# Sheet3.net
KiCad netlist of a schematic drawn in Altium Designer
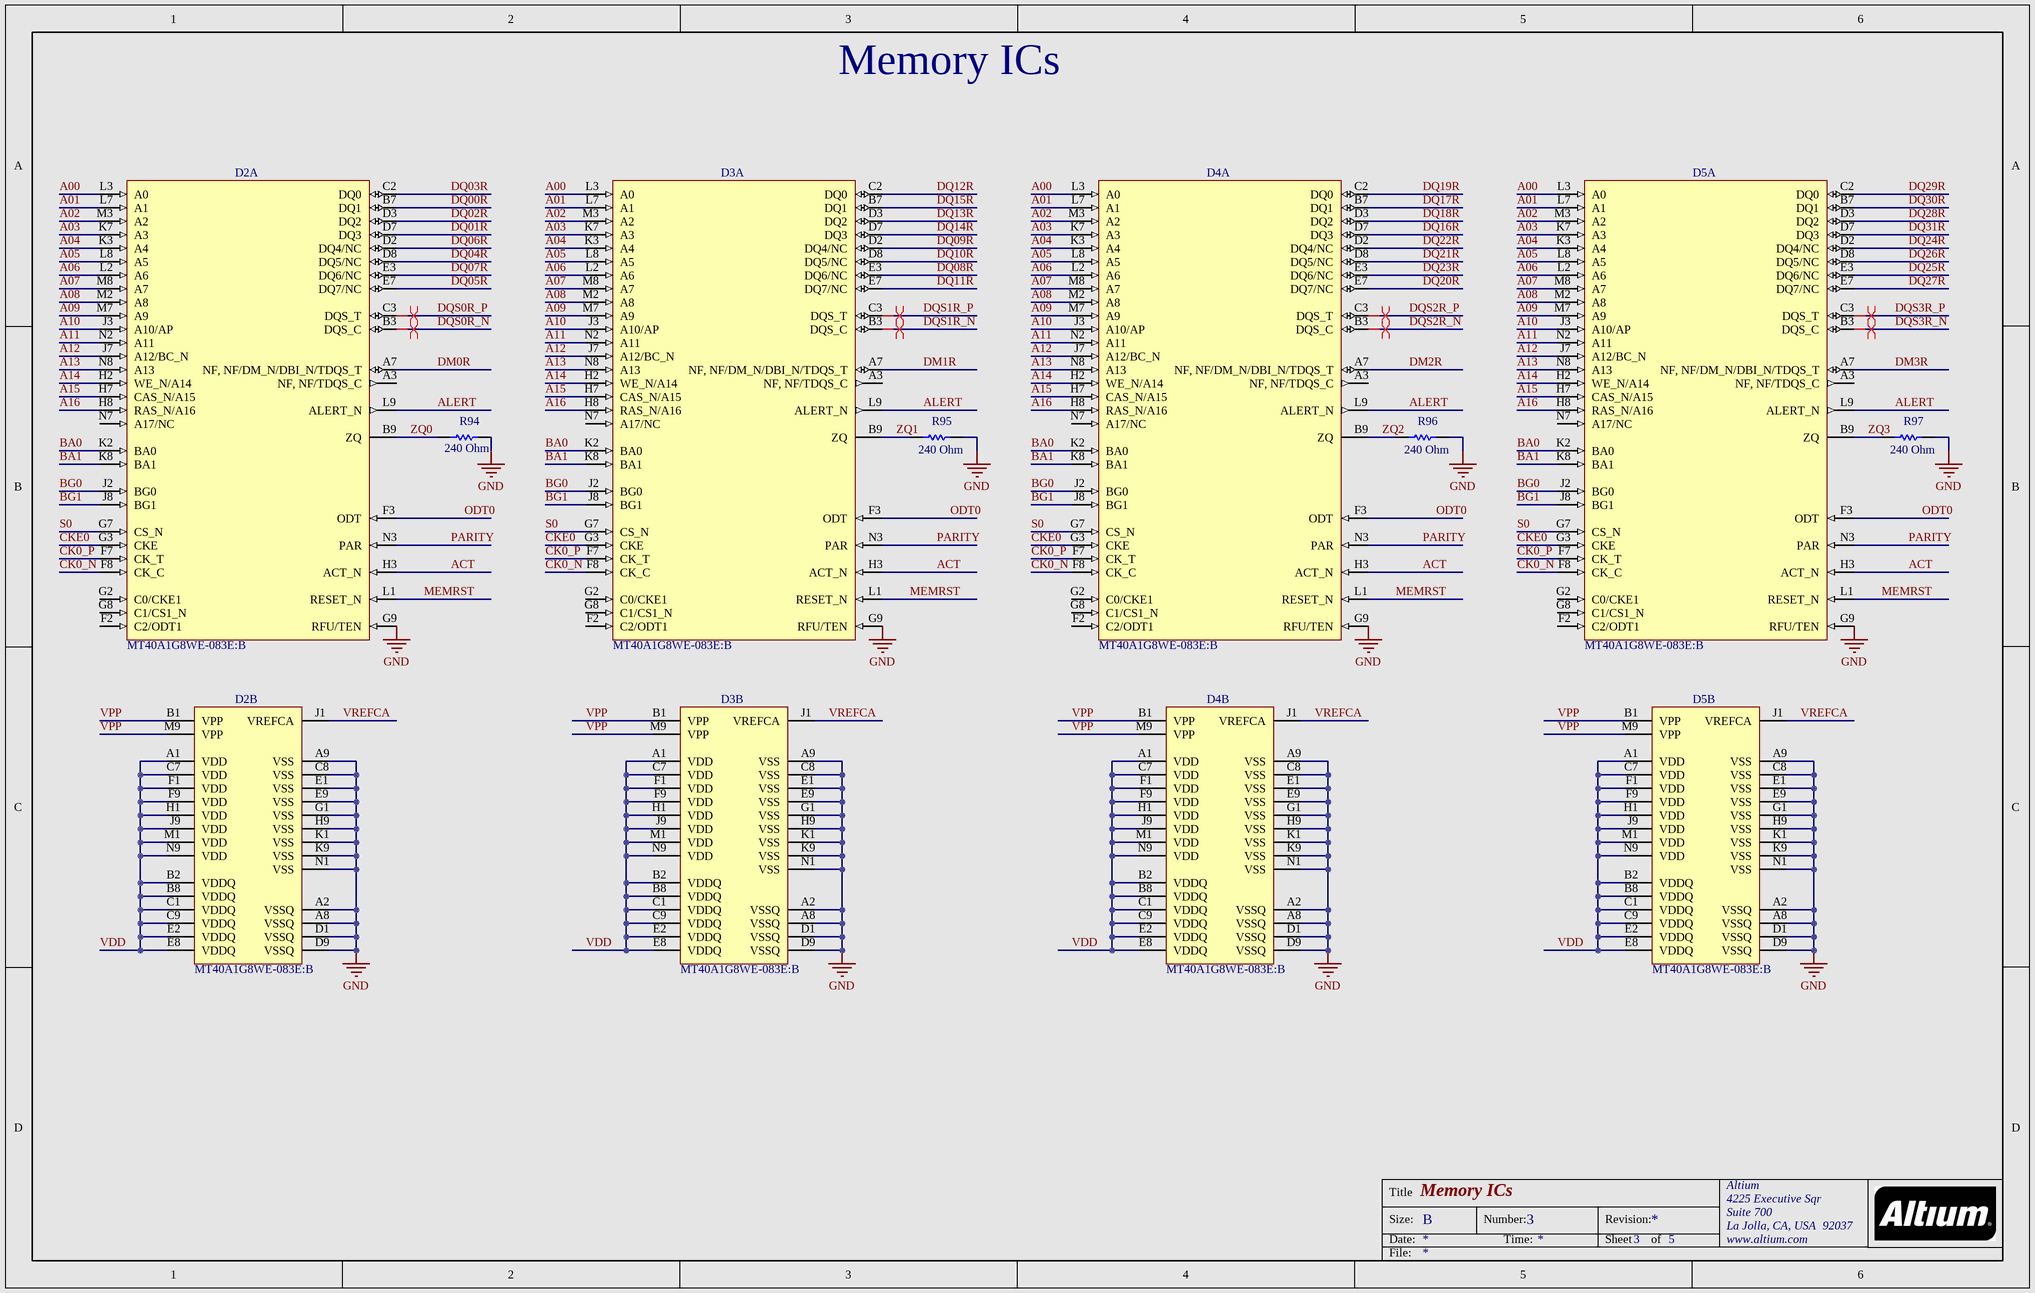
[diagram p0: Sheet3.SchDoc]

(export (version "E")
  (design (tool "Eeschema 10.0.6"))
  (components
    (comp (ref "D2")
      (value "MT40A1G8WE-083E:B")
      (footprint "MICT-WE-78")
      (description "8 Gb DDR4 SDRAM, 1 Gig x 8, 1.2 V, 0 to 95 degC, 78-Ball FBGA (WE), RoHS")
      (libsource (lib "Altium Content Vault") (part "CMP-1738-00001-1"))
    )
    (comp (ref "D3")
      (value "MT40A1G8WE-083E:B")
      (footprint "MICT-WE-78")
      (description "8 Gb DDR4 SDRAM, 1 Gig x 8, 1.2 V, 0 to 95 degC, 78-Ball FBGA (WE), RoHS")
      (libsource (lib "Altium Content Vault") (part "CMP-1738-00001-1"))
    )
    (comp (ref "D4")
      (value "MT40A1G8WE-083E:B")
      (footprint "MICT-WE-78")
      (description "8 Gb DDR4 SDRAM, 1 Gig x 8, 1.2 V, 0 to 95 degC, 78-Ball FBGA (WE), RoHS")
      (libsource (lib "Altium Content Vault") (part "CMP-1738-00001-1"))
    )
    (comp (ref "D5")
      (value "MT40A1G8WE-083E:B")
      (footprint "MICT-WE-78")
      (description "8 Gb DDR4 SDRAM, 1 Gig x 8, 1.2 V, 0 to 95 degC, 78-Ball FBGA (WE), RoHS")
      (libsource (lib "Altium Content Vault") (part "CMP-1738-00001-1"))
    )
    (comp (ref "R94")
      (value "ERJ-2GEJ241x")
      (footprint "RESC1005X40X25ML05T05")
      (description "Chip Resistor, 240 Ohm, +/- 5%, 100 mW, -55 to 155 degC, 0402 (1005 Metric), RoHS, Tape and Reel")
      (fields
        (field (name "RESISTANCE") "240 Ohm")
        (field (name "TOLERANCE") "5%")
        (field (name "MANUFACTURER") "Basic Passives")
      )
      (libsource (lib "Altium Content Vault") (part "CMP-2002-00493-3"))
    )
    (comp (ref "R95")
      (value "ERJ-2GEJ241x")
      (footprint "RESC1005X40X25ML05T05")
      (description "Chip Resistor, 240 Ohm, +/- 5%, 100 mW, -55 to 155 degC, 0402 (1005 Metric), RoHS, Tape and Reel")
      (fields
        (field (name "RESISTANCE") "240 Ohm")
        (field (name "TOLERANCE") "5%")
        (field (name "MANUFACTURER") "Basic Passives")
      )
      (libsource (lib "Altium Content Vault") (part "CMP-2002-00493-3"))
    )
    (comp (ref "R96")
      (value "ERJ-2GEJ241x")
      (footprint "RESC1005X40X25ML05T05")
      (description "Chip Resistor, 240 Ohm, +/- 5%, 100 mW, -55 to 155 degC, 0402 (1005 Metric), RoHS, Tape and Reel")
      (fields
        (field (name "RESISTANCE") "240 Ohm")
        (field (name "TOLERANCE") "5%")
        (field (name "MANUFACTURER") "Basic Passives")
      )
      (libsource (lib "Altium Content Vault") (part "CMP-2002-00493-3"))
    )
    (comp (ref "R97")
      (value "ERJ-2GEJ241x")
      (footprint "RESC1005X40X25ML05T05")
      (description "Chip Resistor, 240 Ohm, +/- 5%, 100 mW, -55 to 155 degC, 0402 (1005 Metric), RoHS, Tape and Reel")
      (fields
        (field (name "RESISTANCE") "240 Ohm")
        (field (name "TOLERANCE") "5%")
        (field (name "MANUFACTURER") "Basic Passives")
      )
      (libsource (lib "Altium Content Vault") (part "CMP-2002-00493-3"))
    )
  )
  (nets
    (net (code "1") (name "/A00") (class "Default")
      (node (ref "D2") (pin "L3") (pinfunction "A0_L3") (pintype "input"))
      (node (ref "D3") (pin "L3") (pinfunction "A0_L3") (pintype "input"))
      (node (ref "D4") (pin "L3") (pinfunction "A0_L3") (pintype "input"))
      (node (ref "D5") (pin "L3") (pinfunction "A0_L3") (pintype "input"))
    )
    (net (code "2") (name "/A01") (class "Default")
      (node (ref "D2") (pin "L7") (pinfunction "A1_L7") (pintype "input"))
      (node (ref "D3") (pin "L7") (pinfunction "A1_L7") (pintype "input"))
      (node (ref "D4") (pin "L7") (pinfunction "A1_L7") (pintype "input"))
      (node (ref "D5") (pin "L7") (pinfunction "A1_L7") (pintype "input"))
    )
    (net (code "3") (name "/A02") (class "Default")
      (node (ref "D2") (pin "M3") (pinfunction "A2_M3") (pintype "input"))
      (node (ref "D3") (pin "M3") (pinfunction "A2_M3") (pintype "input"))
      (node (ref "D4") (pin "M3") (pinfunction "A2_M3") (pintype "input"))
      (node (ref "D5") (pin "M3") (pinfunction "A2_M3") (pintype "input"))
    )
    (net (code "4") (name "/A03") (class "Default")
      (node (ref "D2") (pin "K7") (pinfunction "A3_K7") (pintype "input"))
      (node (ref "D3") (pin "K7") (pinfunction "A3_K7") (pintype "input"))
      (node (ref "D4") (pin "K7") (pinfunction "A3_K7") (pintype "input"))
      (node (ref "D5") (pin "K7") (pinfunction "A3_K7") (pintype "input"))
    )
    (net (code "5") (name "/A04") (class "Default")
      (node (ref "D2") (pin "K3") (pinfunction "A4_K3") (pintype "input"))
      (node (ref "D3") (pin "K3") (pinfunction "A4_K3") (pintype "input"))
      (node (ref "D4") (pin "K3") (pinfunction "A4_K3") (pintype "input"))
      (node (ref "D5") (pin "K3") (pinfunction "A4_K3") (pintype "input"))
    )
    (net (code "6") (name "/A05") (class "Default")
      (node (ref "D2") (pin "L8") (pinfunction "A5_L8") (pintype "input"))
      (node (ref "D3") (pin "L8") (pinfunction "A5_L8") (pintype "input"))
      (node (ref "D4") (pin "L8") (pinfunction "A5_L8") (pintype "input"))
      (node (ref "D5") (pin "L8") (pinfunction "A5_L8") (pintype "input"))
    )
    (net (code "7") (name "/A06") (class "Default")
      (node (ref "D2") (pin "L2") (pinfunction "A6_L2") (pintype "input"))
      (node (ref "D3") (pin "L2") (pinfunction "A6_L2") (pintype "input"))
      (node (ref "D4") (pin "L2") (pinfunction "A6_L2") (pintype "input"))
      (node (ref "D5") (pin "L2") (pinfunction "A6_L2") (pintype "input"))
    )
    (net (code "8") (name "/A07") (class "Default")
      (node (ref "D2") (pin "M8") (pinfunction "A7_M8") (pintype "input"))
      (node (ref "D3") (pin "M8") (pinfunction "A7_M8") (pintype "input"))
      (node (ref "D4") (pin "M8") (pinfunction "A7_M8") (pintype "input"))
      (node (ref "D5") (pin "M8") (pinfunction "A7_M8") (pintype "input"))
    )
    (net (code "9") (name "/A08") (class "Default")
      (node (ref "D2") (pin "M2") (pinfunction "A8_M2") (pintype "input"))
      (node (ref "D3") (pin "M2") (pinfunction "A8_M2") (pintype "input"))
      (node (ref "D4") (pin "M2") (pinfunction "A8_M2") (pintype "input"))
      (node (ref "D5") (pin "M2") (pinfunction "A8_M2") (pintype "input"))
    )
    (net (code "10") (name "/A09") (class "Default")
      (node (ref "D2") (pin "M7") (pinfunction "A9_M7") (pintype "input"))
      (node (ref "D3") (pin "M7") (pinfunction "A9_M7") (pintype "input"))
      (node (ref "D4") (pin "M7") (pinfunction "A9_M7") (pintype "input"))
      (node (ref "D5") (pin "M7") (pinfunction "A9_M7") (pintype "input"))
    )
    (net (code "11") (name "/A10") (class "Default")
      (node (ref "D2") (pin "J3") (pinfunction "A10/AP_J3") (pintype "input"))
      (node (ref "D3") (pin "J3") (pinfunction "A10/AP_J3") (pintype "input"))
      (node (ref "D4") (pin "J3") (pinfunction "A10/AP_J3") (pintype "input"))
      (node (ref "D5") (pin "J3") (pinfunction "A10/AP_J3") (pintype "input"))
    )
    (net (code "12") (name "/A11") (class "Default")
      (node (ref "D2") (pin "N2") (pinfunction "A11_N2") (pintype "input"))
      (node (ref "D3") (pin "N2") (pinfunction "A11_N2") (pintype "input"))
      (node (ref "D4") (pin "N2") (pinfunction "A11_N2") (pintype "input"))
      (node (ref "D5") (pin "N2") (pinfunction "A11_N2") (pintype "input"))
    )
    (net (code "13") (name "/A12") (class "Default")
      (node (ref "D2") (pin "J7") (pinfunction "A12/BC_N_J7") (pintype "input"))
      (node (ref "D3") (pin "J7") (pinfunction "A12/BC_N_J7") (pintype "input"))
      (node (ref "D4") (pin "J7") (pinfunction "A12/BC_N_J7") (pintype "input"))
      (node (ref "D5") (pin "J7") (pinfunction "A12/BC_N_J7") (pintype "input"))
    )
    (net (code "14") (name "/A13") (class "Default")
      (node (ref "D2") (pin "N8") (pinfunction "A13_N8") (pintype "input"))
      (node (ref "D3") (pin "N8") (pinfunction "A13_N8") (pintype "input"))
      (node (ref "D4") (pin "N8") (pinfunction "A13_N8") (pintype "input"))
      (node (ref "D5") (pin "N8") (pinfunction "A13_N8") (pintype "input"))
    )
    (net (code "15") (name "/A14") (class "Default")
      (node (ref "D2") (pin "H2") (pinfunction "WE_N/A14_H2") (pintype "input"))
      (node (ref "D3") (pin "H2") (pinfunction "WE_N/A14_H2") (pintype "input"))
      (node (ref "D4") (pin "H2") (pinfunction "WE_N/A14_H2") (pintype "input"))
      (node (ref "D5") (pin "H2") (pinfunction "WE_N/A14_H2") (pintype "input"))
    )
    (net (code "16") (name "/A15") (class "Default")
      (node (ref "D2") (pin "H7") (pinfunction "CAS_N/A15_H7") (pintype "input"))
      (node (ref "D3") (pin "H7") (pinfunction "CAS_N/A15_H7") (pintype "input"))
      (node (ref "D4") (pin "H7") (pinfunction "CAS_N/A15_H7") (pintype "input"))
      (node (ref "D5") (pin "H7") (pinfunction "CAS_N/A15_H7") (pintype "input"))
    )
    (net (code "17") (name "/A16") (class "Default")
      (node (ref "D2") (pin "H8") (pinfunction "RAS_N/A16_H8") (pintype "input"))
      (node (ref "D3") (pin "H8") (pinfunction "RAS_N/A16_H8") (pintype "input"))
      (node (ref "D4") (pin "H8") (pinfunction "RAS_N/A16_H8") (pintype "input"))
      (node (ref "D5") (pin "H8") (pinfunction "RAS_N/A16_H8") (pintype "input"))
    )
    (net (code "18") (name "/ACT") (class "Default")
      (node (ref "D2") (pin "H3") (pinfunction "ACT_N_H3") (pintype "input"))
      (node (ref "D3") (pin "H3") (pinfunction "ACT_N_H3") (pintype "input"))
      (node (ref "D4") (pin "H3") (pinfunction "ACT_N_H3") (pintype "input"))
      (node (ref "D5") (pin "H3") (pinfunction "ACT_N_H3") (pintype "input"))
    )
    (net (code "19") (name "/ALERT") (class "Default")
      (node (ref "D2") (pin "L9") (pinfunction "ALERT_N_L9") (pintype "output"))
      (node (ref "D3") (pin "L9") (pinfunction "ALERT_N_L9") (pintype "output"))
      (node (ref "D4") (pin "L9") (pinfunction "ALERT_N_L9") (pintype "output"))
      (node (ref "D5") (pin "L9") (pinfunction "ALERT_N_L9") (pintype "output"))
    )
    (net (code "20") (name "/BA0") (class "Default")
      (node (ref "D2") (pin "K2") (pinfunction "BA0_K2") (pintype "input"))
      (node (ref "D3") (pin "K2") (pinfunction "BA0_K2") (pintype "input"))
      (node (ref "D4") (pin "K2") (pinfunction "BA0_K2") (pintype "input"))
      (node (ref "D5") (pin "K2") (pinfunction "BA0_K2") (pintype "input"))
    )
    (net (code "21") (name "/BA1") (class "Default")
      (node (ref "D2") (pin "K8") (pinfunction "BA1_K8") (pintype "input"))
      (node (ref "D3") (pin "K8") (pinfunction "BA1_K8") (pintype "input"))
      (node (ref "D4") (pin "K8") (pinfunction "BA1_K8") (pintype "input"))
      (node (ref "D5") (pin "K8") (pinfunction "BA1_K8") (pintype "input"))
    )
    (net (code "22") (name "/BG0") (class "Default")
      (node (ref "D2") (pin "J2") (pinfunction "BG0_J2") (pintype "input"))
      (node (ref "D3") (pin "J2") (pinfunction "BG0_J2") (pintype "input"))
      (node (ref "D4") (pin "J2") (pinfunction "BG0_J2") (pintype "input"))
      (node (ref "D5") (pin "J2") (pinfunction "BG0_J2") (pintype "input"))
    )
    (net (code "23") (name "/BG1") (class "Default")
      (node (ref "D2") (pin "J8") (pinfunction "BG1_J8") (pintype "input"))
      (node (ref "D3") (pin "J8") (pinfunction "BG1_J8") (pintype "input"))
      (node (ref "D4") (pin "J8") (pinfunction "BG1_J8") (pintype "input"))
      (node (ref "D5") (pin "J8") (pinfunction "BG1_J8") (pintype "input"))
    )
    (net (code "24") (name "/CK0_N") (class "Default")
      (node (ref "D2") (pin "F8") (pinfunction "CK_C_F8") (pintype "input"))
      (node (ref "D3") (pin "F8") (pinfunction "CK_C_F8") (pintype "input"))
      (node (ref "D4") (pin "F8") (pinfunction "CK_C_F8") (pintype "input"))
      (node (ref "D5") (pin "F8") (pinfunction "CK_C_F8") (pintype "input"))
    )
    (net (code "25") (name "/CK0_P") (class "Default")
      (node (ref "D2") (pin "F7") (pinfunction "CK_T_F7") (pintype "input"))
      (node (ref "D3") (pin "F7") (pinfunction "CK_T_F7") (pintype "input"))
      (node (ref "D4") (pin "F7") (pinfunction "CK_T_F7") (pintype "input"))
      (node (ref "D5") (pin "F7") (pinfunction "CK_T_F7") (pintype "input"))
    )
    (net (code "26") (name "/CKE0") (class "Default")
      (node (ref "D2") (pin "G3") (pinfunction "CKE_G3") (pintype "input"))
      (node (ref "D3") (pin "G3") (pinfunction "CKE_G3") (pintype "input"))
      (node (ref "D4") (pin "G3") (pinfunction "CKE_G3") (pintype "input"))
      (node (ref "D5") (pin "G3") (pinfunction "CKE_G3") (pintype "input"))
    )
    (net (code "27") (name "/DM0R") (class "Default")
      (node (ref "D2") (pin "A7") (pinfunction "NF,_NF/DM_N/DBI_N/TDQS_T_A7") (pintype "bidirectional"))
    )
    (net (code "28") (name "/DM1R") (class "Default")
      (node (ref "D3") (pin "A7") (pinfunction "NF,_NF/DM_N/DBI_N/TDQS_T_A7") (pintype "bidirectional"))
    )
    (net (code "29") (name "/DM2R") (class "Default")
      (node (ref "D4") (pin "A7") (pinfunction "NF,_NF/DM_N/DBI_N/TDQS_T_A7") (pintype "bidirectional"))
    )
    (net (code "30") (name "/DM3R") (class "Default")
      (node (ref "D5") (pin "A7") (pinfunction "NF,_NF/DM_N/DBI_N/TDQS_T_A7") (pintype "bidirectional"))
    )
    (net (code "31") (name "/DQ00R") (class "Default")
      (node (ref "D2") (pin "B7") (pinfunction "DQ1_B7") (pintype "bidirectional"))
    )
    (net (code "32") (name "/DQ01R") (class "Default")
      (node (ref "D2") (pin "D7") (pinfunction "DQ3_D7") (pintype "bidirectional"))
    )
    (net (code "33") (name "/DQ02R") (class "Default")
      (node (ref "D2") (pin "D3") (pinfunction "DQ2_D3") (pintype "bidirectional"))
    )
    (net (code "34") (name "/DQ03R") (class "Default")
      (node (ref "D2") (pin "C2") (pinfunction "DQ0_C2") (pintype "bidirectional"))
    )
    (net (code "35") (name "/DQ04R") (class "Default")
      (node (ref "D2") (pin "D8") (pinfunction "DQ5/NC_D8") (pintype "bidirectional"))
    )
    (net (code "36") (name "/DQ05R") (class "Default")
      (node (ref "D2") (pin "E7") (pinfunction "DQ7/NC_E7") (pintype "bidirectional"))
    )
    (net (code "37") (name "/DQ06R") (class "Default")
      (node (ref "D2") (pin "D2") (pinfunction "DQ4/NC_D2") (pintype "bidirectional"))
    )
    (net (code "38") (name "/DQ07R") (class "Default")
      (node (ref "D2") (pin "E3") (pinfunction "DQ6/NC_E3") (pintype "bidirectional"))
    )
    (net (code "39") (name "/DQ08R") (class "Default")
      (node (ref "D3") (pin "E3") (pinfunction "DQ6/NC_E3") (pintype "bidirectional"))
    )
    (net (code "40") (name "/DQ09R") (class "Default")
      (node (ref "D3") (pin "D2") (pinfunction "DQ4/NC_D2") (pintype "bidirectional"))
    )
    (net (code "41") (name "/DQ10R") (class "Default")
      (node (ref "D3") (pin "D8") (pinfunction "DQ5/NC_D8") (pintype "bidirectional"))
    )
    (net (code "42") (name "/DQ11R") (class "Default")
      (node (ref "D3") (pin "E7") (pinfunction "DQ7/NC_E7") (pintype "bidirectional"))
    )
    (net (code "43") (name "/DQ12R") (class "Default")
      (node (ref "D3") (pin "C2") (pinfunction "DQ0_C2") (pintype "bidirectional"))
    )
    (net (code "44") (name "/DQ13R") (class "Default")
      (node (ref "D3") (pin "D3") (pinfunction "DQ2_D3") (pintype "bidirectional"))
    )
    (net (code "45") (name "/DQ14R") (class "Default")
      (node (ref "D3") (pin "D7") (pinfunction "DQ3_D7") (pintype "bidirectional"))
    )
    (net (code "46") (name "/DQ15R") (class "Default")
      (node (ref "D3") (pin "B7") (pinfunction "DQ1_B7") (pintype "bidirectional"))
    )
    (net (code "47") (name "/DQ16R") (class "Default")
      (node (ref "D4") (pin "D7") (pinfunction "DQ3_D7") (pintype "bidirectional"))
    )
    (net (code "48") (name "/DQ17R") (class "Default")
      (node (ref "D4") (pin "B7") (pinfunction "DQ1_B7") (pintype "bidirectional"))
    )
    (net (code "49") (name "/DQ18R") (class "Default")
      (node (ref "D4") (pin "D3") (pinfunction "DQ2_D3") (pintype "bidirectional"))
    )
    (net (code "50") (name "/DQ19R") (class "Default")
      (node (ref "D4") (pin "C2") (pinfunction "DQ0_C2") (pintype "bidirectional"))
    )
    (net (code "51") (name "/DQ20R") (class "Default")
      (node (ref "D4") (pin "E7") (pinfunction "DQ7/NC_E7") (pintype "bidirectional"))
    )
    (net (code "52") (name "/DQ21R") (class "Default")
      (node (ref "D4") (pin "D8") (pinfunction "DQ5/NC_D8") (pintype "bidirectional"))
    )
    (net (code "53") (name "/DQ22R") (class "Default")
      (node (ref "D4") (pin "D2") (pinfunction "DQ4/NC_D2") (pintype "bidirectional"))
    )
    (net (code "54") (name "/DQ23R") (class "Default")
      (node (ref "D4") (pin "E3") (pinfunction "DQ6/NC_E3") (pintype "bidirectional"))
    )
    (net (code "55") (name "/DQ24R") (class "Default")
      (node (ref "D5") (pin "D2") (pinfunction "DQ4/NC_D2") (pintype "bidirectional"))
    )
    (net (code "56") (name "/DQ25R") (class "Default")
      (node (ref "D5") (pin "E3") (pinfunction "DQ6/NC_E3") (pintype "bidirectional"))
    )
    (net (code "57") (name "/DQ26R") (class "Default")
      (node (ref "D5") (pin "D8") (pinfunction "DQ5/NC_D8") (pintype "bidirectional"))
    )
    (net (code "58") (name "/DQ27R") (class "Default")
      (node (ref "D5") (pin "E7") (pinfunction "DQ7/NC_E7") (pintype "bidirectional"))
    )
    (net (code "59") (name "/DQ28R") (class "Default")
      (node (ref "D5") (pin "D3") (pinfunction "DQ2_D3") (pintype "bidirectional"))
    )
    (net (code "60") (name "/DQ29R") (class "Default")
      (node (ref "D5") (pin "C2") (pinfunction "DQ0_C2") (pintype "bidirectional"))
    )
    (net (code "61") (name "/DQ30R") (class "Default")
      (node (ref "D5") (pin "B7") (pinfunction "DQ1_B7") (pintype "bidirectional"))
    )
    (net (code "62") (name "/DQ31R") (class "Default")
      (node (ref "D5") (pin "D7") (pinfunction "DQ3_D7") (pintype "bidirectional"))
    )
    (net (code "63") (name "/DQS0R_N") (class "Default")
      (node (ref "D2") (pin "B3") (pinfunction "DQS_C_B3") (pintype "bidirectional"))
    )
    (net (code "64") (name "/DQS0R_P") (class "Default")
      (node (ref "D2") (pin "C3") (pinfunction "DQS_T_C3") (pintype "bidirectional"))
    )
    (net (code "65") (name "/DQS1R_N") (class "Default")
      (node (ref "D3") (pin "B3") (pinfunction "DQS_C_B3") (pintype "bidirectional"))
    )
    (net (code "66") (name "/DQS1R_P") (class "Default")
      (node (ref "D3") (pin "C3") (pinfunction "DQS_T_C3") (pintype "bidirectional"))
    )
    (net (code "67") (name "/DQS2R_N") (class "Default")
      (node (ref "D4") (pin "B3") (pinfunction "DQS_C_B3") (pintype "bidirectional"))
    )
    (net (code "68") (name "/DQS2R_P") (class "Default")
      (node (ref "D4") (pin "C3") (pinfunction "DQS_T_C3") (pintype "bidirectional"))
    )
    (net (code "69") (name "/DQS3R_N") (class "Default")
      (node (ref "D5") (pin "B3") (pinfunction "DQS_C_B3") (pintype "bidirectional"))
    )
    (net (code "70") (name "/DQS3R_P") (class "Default")
      (node (ref "D5") (pin "C3") (pinfunction "DQS_T_C3") (pintype "bidirectional"))
    )
    (net (code "71") (name "/MEMRST") (class "Default")
      (node (ref "D2") (pin "L1") (pinfunction "RESET_N_L1") (pintype "input"))
      (node (ref "D3") (pin "L1") (pinfunction "RESET_N_L1") (pintype "input"))
      (node (ref "D4") (pin "L1") (pinfunction "RESET_N_L1") (pintype "input"))
      (node (ref "D5") (pin "L1") (pinfunction "RESET_N_L1") (pintype "input"))
    )
    (net (code "72") (name "/ODT0") (class "Default")
      (node (ref "D2") (pin "F3") (pinfunction "ODT_F3") (pintype "input"))
      (node (ref "D3") (pin "F3") (pinfunction "ODT_F3") (pintype "input"))
      (node (ref "D4") (pin "F3") (pinfunction "ODT_F3") (pintype "input"))
      (node (ref "D5") (pin "F3") (pinfunction "ODT_F3") (pintype "input"))
    )
    (net (code "73") (name "/PARITY") (class "Default")
      (node (ref "D2") (pin "N3") (pinfunction "PAR_N3") (pintype "input"))
      (node (ref "D3") (pin "N3") (pinfunction "PAR_N3") (pintype "input"))
      (node (ref "D4") (pin "N3") (pinfunction "PAR_N3") (pintype "input"))
      (node (ref "D5") (pin "N3") (pinfunction "PAR_N3") (pintype "input"))
    )
    (net (code "74") (name "/S0") (class "Default")
      (node (ref "D2") (pin "G7") (pinfunction "CS_N_G7") (pintype "input"))
      (node (ref "D3") (pin "G7") (pinfunction "CS_N_G7") (pintype "input"))
      (node (ref "D4") (pin "G7") (pinfunction "CS_N_G7") (pintype "input"))
      (node (ref "D5") (pin "G7") (pinfunction "CS_N_G7") (pintype "input"))
    )
    (net (code "75") (name "/VDD") (class "Default")
      (node (ref "D2") (pin "A1") (pinfunction "VDD_A1") (pintype "power_in"))
      (node (ref "D2") (pin "B2") (pinfunction "VDDQ_B2") (pintype "power_in"))
      (node (ref "D2") (pin "B8") (pinfunction "VDDQ_B8") (pintype "power_in"))
      (node (ref "D2") (pin "C1") (pinfunction "VDDQ_C1") (pintype "power_in"))
      (node (ref "D2") (pin "C7") (pinfunction "VDD_C7") (pintype "power_in"))
      (node (ref "D2") (pin "C9") (pinfunction "VDDQ_C9") (pintype "power_in"))
      (node (ref "D2") (pin "E2") (pinfunction "VDDQ_E2") (pintype "power_in"))
      (node (ref "D2") (pin "E8") (pinfunction "VDDQ_E8") (pintype "power_in"))
      (node (ref "D2") (pin "F1") (pinfunction "VDD_F1") (pintype "power_in"))
      (node (ref "D2") (pin "F9") (pinfunction "VDD_F9") (pintype "power_in"))
      (node (ref "D2") (pin "H1") (pinfunction "VDD_H1") (pintype "power_in"))
      (node (ref "D2") (pin "J9") (pinfunction "VDD_J9") (pintype "power_in"))
      (node (ref "D2") (pin "M1") (pinfunction "VDD_M1") (pintype "power_in"))
      (node (ref "D2") (pin "N9") (pinfunction "VDD_N9") (pintype "power_in"))
      (node (ref "D3") (pin "A1") (pinfunction "VDD_A1") (pintype "power_in"))
      (node (ref "D3") (pin "B2") (pinfunction "VDDQ_B2") (pintype "power_in"))
      (node (ref "D3") (pin "B8") (pinfunction "VDDQ_B8") (pintype "power_in"))
      (node (ref "D3") (pin "C1") (pinfunction "VDDQ_C1") (pintype "power_in"))
      (node (ref "D3") (pin "C7") (pinfunction "VDD_C7") (pintype "power_in"))
      (node (ref "D3") (pin "C9") (pinfunction "VDDQ_C9") (pintype "power_in"))
      (node (ref "D3") (pin "E2") (pinfunction "VDDQ_E2") (pintype "power_in"))
      (node (ref "D3") (pin "E8") (pinfunction "VDDQ_E8") (pintype "power_in"))
      (node (ref "D3") (pin "F1") (pinfunction "VDD_F1") (pintype "power_in"))
      (node (ref "D3") (pin "F9") (pinfunction "VDD_F9") (pintype "power_in"))
      (node (ref "D3") (pin "H1") (pinfunction "VDD_H1") (pintype "power_in"))
      (node (ref "D3") (pin "J9") (pinfunction "VDD_J9") (pintype "power_in"))
      (node (ref "D3") (pin "M1") (pinfunction "VDD_M1") (pintype "power_in"))
      (node (ref "D3") (pin "N9") (pinfunction "VDD_N9") (pintype "power_in"))
      (node (ref "D4") (pin "A1") (pinfunction "VDD_A1") (pintype "power_in"))
      (node (ref "D4") (pin "B2") (pinfunction "VDDQ_B2") (pintype "power_in"))
      (node (ref "D4") (pin "B8") (pinfunction "VDDQ_B8") (pintype "power_in"))
      (node (ref "D4") (pin "C1") (pinfunction "VDDQ_C1") (pintype "power_in"))
      (node (ref "D4") (pin "C7") (pinfunction "VDD_C7") (pintype "power_in"))
      (node (ref "D4") (pin "C9") (pinfunction "VDDQ_C9") (pintype "power_in"))
      (node (ref "D4") (pin "E2") (pinfunction "VDDQ_E2") (pintype "power_in"))
      (node (ref "D4") (pin "E8") (pinfunction "VDDQ_E8") (pintype "power_in"))
      (node (ref "D4") (pin "F1") (pinfunction "VDD_F1") (pintype "power_in"))
      (node (ref "D4") (pin "F9") (pinfunction "VDD_F9") (pintype "power_in"))
      (node (ref "D4") (pin "H1") (pinfunction "VDD_H1") (pintype "power_in"))
      (node (ref "D4") (pin "J9") (pinfunction "VDD_J9") (pintype "power_in"))
      (node (ref "D4") (pin "M1") (pinfunction "VDD_M1") (pintype "power_in"))
      (node (ref "D4") (pin "N9") (pinfunction "VDD_N9") (pintype "power_in"))
      (node (ref "D5") (pin "A1") (pinfunction "VDD_A1") (pintype "power_in"))
      (node (ref "D5") (pin "B2") (pinfunction "VDDQ_B2") (pintype "power_in"))
      (node (ref "D5") (pin "B8") (pinfunction "VDDQ_B8") (pintype "power_in"))
      (node (ref "D5") (pin "C1") (pinfunction "VDDQ_C1") (pintype "power_in"))
      (node (ref "D5") (pin "C7") (pinfunction "VDD_C7") (pintype "power_in"))
      (node (ref "D5") (pin "C9") (pinfunction "VDDQ_C9") (pintype "power_in"))
      (node (ref "D5") (pin "E2") (pinfunction "VDDQ_E2") (pintype "power_in"))
      (node (ref "D5") (pin "E8") (pinfunction "VDDQ_E8") (pintype "power_in"))
      (node (ref "D5") (pin "F1") (pinfunction "VDD_F1") (pintype "power_in"))
      (node (ref "D5") (pin "F9") (pinfunction "VDD_F9") (pintype "power_in"))
      (node (ref "D5") (pin "H1") (pinfunction "VDD_H1") (pintype "power_in"))
      (node (ref "D5") (pin "J9") (pinfunction "VDD_J9") (pintype "power_in"))
      (node (ref "D5") (pin "M1") (pinfunction "VDD_M1") (pintype "power_in"))
      (node (ref "D5") (pin "N9") (pinfunction "VDD_N9") (pintype "power_in"))
    )
    (net (code "76") (name "/VPP") (class "Default")
      (node (ref "D2") (pin "B1") (pinfunction "VPP_B1") (pintype "power_in"))
      (node (ref "D2") (pin "M9") (pinfunction "VPP_M9") (pintype "power_in"))
      (node (ref "D3") (pin "B1") (pinfunction "VPP_B1") (pintype "power_in"))
      (node (ref "D3") (pin "M9") (pinfunction "VPP_M9") (pintype "power_in"))
      (node (ref "D4") (pin "B1") (pinfunction "VPP_B1") (pintype "power_in"))
      (node (ref "D4") (pin "M9") (pinfunction "VPP_M9") (pintype "power_in"))
      (node (ref "D5") (pin "B1") (pinfunction "VPP_B1") (pintype "power_in"))
      (node (ref "D5") (pin "M9") (pinfunction "VPP_M9") (pintype "power_in"))
    )
    (net (code "77") (name "/VREFCA") (class "Default")
      (node (ref "D2") (pin "J1") (pinfunction "VREFCA_J1") (pintype "passive"))
      (node (ref "D3") (pin "J1") (pinfunction "VREFCA_J1") (pintype "passive"))
      (node (ref "D4") (pin "J1") (pinfunction "VREFCA_J1") (pintype "passive"))
      (node (ref "D5") (pin "J1") (pinfunction "VREFCA_J1") (pintype "passive"))
    )
    (net (code "78") (name "/ZQ0") (class "Default")
      (node (ref "D2") (pin "B9") (pinfunction "ZQ_B9") (pintype "passive"))
      (node (ref "R94") (pin "2") (pinfunction "2_2") (pintype "passive"))
    )
    (net (code "79") (name "/ZQ1") (class "Default")
      (node (ref "D3") (pin "B9") (pinfunction "ZQ_B9") (pintype "passive"))
      (node (ref "R95") (pin "2") (pinfunction "2_2") (pintype "passive"))
    )
    (net (code "80") (name "/ZQ2") (class "Default")
      (node (ref "D4") (pin "B9") (pinfunction "ZQ_B9") (pintype "passive"))
      (node (ref "R96") (pin "2") (pinfunction "2_2") (pintype "passive"))
    )
    (net (code "81") (name "/ZQ3") (class "Default")
      (node (ref "D5") (pin "B9") (pinfunction "ZQ_B9") (pintype "passive"))
      (node (ref "R97") (pin "2") (pinfunction "2_2") (pintype "passive"))
    )
    (net (code "82") (name "GND") (class "Default")
      (node (ref "D2") (pin "A2") (pinfunction "VSSQ_A2") (pintype "power_in"))
      (node (ref "D2") (pin "A8") (pinfunction "VSSQ_A8") (pintype "power_in"))
      (node (ref "D2") (pin "A9") (pinfunction "VSS_A9") (pintype "power_in"))
      (node (ref "D2") (pin "C8") (pinfunction "VSS_C8") (pintype "power_in"))
      (node (ref "D2") (pin "D1") (pinfunction "VSSQ_D1") (pintype "power_in"))
      (node (ref "D2") (pin "D9") (pinfunction "VSSQ_D9") (pintype "power_in"))
      (node (ref "D2") (pin "E1") (pinfunction "VSS_E1") (pintype "power_in"))
      (node (ref "D2") (pin "E9") (pinfunction "VSS_E9") (pintype "power_in"))
      (node (ref "D2") (pin "G1") (pinfunction "VSS_G1") (pintype "power_in"))
      (node (ref "D2") (pin "G9") (pinfunction "RFU/TEN_G9") (pintype "input"))
      (node (ref "D2") (pin "H9") (pinfunction "VSS_H9") (pintype "power_in"))
      (node (ref "D2") (pin "K1") (pinfunction "VSS_K1") (pintype "power_in"))
      (node (ref "D2") (pin "K9") (pinfunction "VSS_K9") (pintype "power_in"))
      (node (ref "D2") (pin "N1") (pinfunction "VSS_N1") (pintype "power_in"))
      (node (ref "D3") (pin "A2") (pinfunction "VSSQ_A2") (pintype "power_in"))
      (node (ref "D3") (pin "A8") (pinfunction "VSSQ_A8") (pintype "power_in"))
      (node (ref "D3") (pin "A9") (pinfunction "VSS_A9") (pintype "power_in"))
      (node (ref "D3") (pin "C8") (pinfunction "VSS_C8") (pintype "power_in"))
      (node (ref "D3") (pin "D1") (pinfunction "VSSQ_D1") (pintype "power_in"))
      (node (ref "D3") (pin "D9") (pinfunction "VSSQ_D9") (pintype "power_in"))
      (node (ref "D3") (pin "E1") (pinfunction "VSS_E1") (pintype "power_in"))
      (node (ref "D3") (pin "E9") (pinfunction "VSS_E9") (pintype "power_in"))
      (node (ref "D3") (pin "G1") (pinfunction "VSS_G1") (pintype "power_in"))
      (node (ref "D3") (pin "G9") (pinfunction "RFU/TEN_G9") (pintype "input"))
      (node (ref "D3") (pin "H9") (pinfunction "VSS_H9") (pintype "power_in"))
      (node (ref "D3") (pin "K1") (pinfunction "VSS_K1") (pintype "power_in"))
      (node (ref "D3") (pin "K9") (pinfunction "VSS_K9") (pintype "power_in"))
      (node (ref "D3") (pin "N1") (pinfunction "VSS_N1") (pintype "power_in"))
      (node (ref "D4") (pin "A2") (pinfunction "VSSQ_A2") (pintype "power_in"))
      (node (ref "D4") (pin "A8") (pinfunction "VSSQ_A8") (pintype "power_in"))
      (node (ref "D4") (pin "A9") (pinfunction "VSS_A9") (pintype "power_in"))
      (node (ref "D4") (pin "C8") (pinfunction "VSS_C8") (pintype "power_in"))
      (node (ref "D4") (pin "D1") (pinfunction "VSSQ_D1") (pintype "power_in"))
      (node (ref "D4") (pin "D9") (pinfunction "VSSQ_D9") (pintype "power_in"))
      (node (ref "D4") (pin "E1") (pinfunction "VSS_E1") (pintype "power_in"))
      (node (ref "D4") (pin "E9") (pinfunction "VSS_E9") (pintype "power_in"))
      (node (ref "D4") (pin "G1") (pinfunction "VSS_G1") (pintype "power_in"))
      (node (ref "D4") (pin "G9") (pinfunction "RFU/TEN_G9") (pintype "input"))
      (node (ref "D4") (pin "H9") (pinfunction "VSS_H9") (pintype "power_in"))
      (node (ref "D4") (pin "K1") (pinfunction "VSS_K1") (pintype "power_in"))
      (node (ref "D4") (pin "K9") (pinfunction "VSS_K9") (pintype "power_in"))
      (node (ref "D4") (pin "N1") (pinfunction "VSS_N1") (pintype "power_in"))
      (node (ref "D5") (pin "A2") (pinfunction "VSSQ_A2") (pintype "power_in"))
      (node (ref "D5") (pin "A8") (pinfunction "VSSQ_A8") (pintype "power_in"))
      (node (ref "D5") (pin "A9") (pinfunction "VSS_A9") (pintype "power_in"))
      (node (ref "D5") (pin "C8") (pinfunction "VSS_C8") (pintype "power_in"))
      (node (ref "D5") (pin "D1") (pinfunction "VSSQ_D1") (pintype "power_in"))
      (node (ref "D5") (pin "D9") (pinfunction "VSSQ_D9") (pintype "power_in"))
      (node (ref "D5") (pin "E1") (pinfunction "VSS_E1") (pintype "power_in"))
      (node (ref "D5") (pin "E9") (pinfunction "VSS_E9") (pintype "power_in"))
      (node (ref "D5") (pin "G1") (pinfunction "VSS_G1") (pintype "power_in"))
      (node (ref "D5") (pin "G9") (pinfunction "RFU/TEN_G9") (pintype "input"))
      (node (ref "D5") (pin "H9") (pinfunction "VSS_H9") (pintype "power_in"))
      (node (ref "D5") (pin "K1") (pinfunction "VSS_K1") (pintype "power_in"))
      (node (ref "D5") (pin "K9") (pinfunction "VSS_K9") (pintype "power_in"))
      (node (ref "D5") (pin "N1") (pinfunction "VSS_N1") (pintype "power_in"))
      (node (ref "R94") (pin "1") (pinfunction "1_1") (pintype "passive"))
      (node (ref "R95") (pin "1") (pinfunction "1_1") (pintype "passive"))
      (node (ref "R96") (pin "1") (pinfunction "1_1") (pintype "passive"))
      (node (ref "R97") (pin "1") (pinfunction "1_1") (pintype "passive"))
    )
    (net (code "83") (name "unconnected-(D2A-A17{slash}NC-PadN7)") (class "Default")
      (node (ref "D2") (pin "N7") (pinfunction "A17/NC_N7") (pintype "input"))
    )
    (net (code "84") (name "unconnected-(D2A-C0{slash}CKE1-PadG2)") (class "Default")
      (node (ref "D2") (pin "G2") (pinfunction "C0/CKE1_G2") (pintype "input"))
    )
    (net (code "85") (name "unconnected-(D2A-C1{slash}CS1_N-PadG8)") (class "Default")
      (node (ref "D2") (pin "G8") (pinfunction "C1/CS1_N_G8") (pintype "input"))
    )
    (net (code "86") (name "unconnected-(D2A-C2{slash}ODT1-PadF2)") (class "Default")
      (node (ref "D2") (pin "F2") (pinfunction "C2/ODT1_F2") (pintype "input"))
    )
    (net (code "87") (name "unconnected-(D2A-NF,_NF{slash}TDQS_C-PadA3)") (class "Default")
      (node (ref "D2") (pin "A3") (pinfunction "NF,_NF/TDQS_C_A3") (pintype "output"))
    )
    (net (code "88") (name "unconnected-(D3A-A17{slash}NC-PadN7)") (class "Default")
      (node (ref "D3") (pin "N7") (pinfunction "A17/NC_N7") (pintype "input"))
    )
    (net (code "89") (name "unconnected-(D3A-C0{slash}CKE1-PadG2)") (class "Default")
      (node (ref "D3") (pin "G2") (pinfunction "C0/CKE1_G2") (pintype "input"))
    )
    (net (code "90") (name "unconnected-(D3A-C1{slash}CS1_N-PadG8)") (class "Default")
      (node (ref "D3") (pin "G8") (pinfunction "C1/CS1_N_G8") (pintype "input"))
    )
    (net (code "91") (name "unconnected-(D3A-C2{slash}ODT1-PadF2)") (class "Default")
      (node (ref "D3") (pin "F2") (pinfunction "C2/ODT1_F2") (pintype "input"))
    )
    (net (code "92") (name "unconnected-(D3A-NF,_NF{slash}TDQS_C-PadA3)") (class "Default")
      (node (ref "D3") (pin "A3") (pinfunction "NF,_NF/TDQS_C_A3") (pintype "output"))
    )
    (net (code "93") (name "unconnected-(D4A-A17{slash}NC-PadN7)") (class "Default")
      (node (ref "D4") (pin "N7") (pinfunction "A17/NC_N7") (pintype "input"))
    )
    (net (code "94") (name "unconnected-(D4A-C0{slash}CKE1-PadG2)") (class "Default")
      (node (ref "D4") (pin "G2") (pinfunction "C0/CKE1_G2") (pintype "input"))
    )
    (net (code "95") (name "unconnected-(D4A-C1{slash}CS1_N-PadG8)") (class "Default")
      (node (ref "D4") (pin "G8") (pinfunction "C1/CS1_N_G8") (pintype "input"))
    )
    (net (code "96") (name "unconnected-(D4A-C2{slash}ODT1-PadF2)") (class "Default")
      (node (ref "D4") (pin "F2") (pinfunction "C2/ODT1_F2") (pintype "input"))
    )
    (net (code "97") (name "unconnected-(D4A-NF,_NF{slash}TDQS_C-PadA3)") (class "Default")
      (node (ref "D4") (pin "A3") (pinfunction "NF,_NF/TDQS_C_A3") (pintype "output"))
    )
    (net (code "98") (name "unconnected-(D5A-A17{slash}NC-PadN7)") (class "Default")
      (node (ref "D5") (pin "N7") (pinfunction "A17/NC_N7") (pintype "input"))
    )
    (net (code "99") (name "unconnected-(D5A-C0{slash}CKE1-PadG2)") (class "Default")
      (node (ref "D5") (pin "G2") (pinfunction "C0/CKE1_G2") (pintype "input"))
    )
    (net (code "100") (name "unconnected-(D5A-C1{slash}CS1_N-PadG8)") (class "Default")
      (node (ref "D5") (pin "G8") (pinfunction "C1/CS1_N_G8") (pintype "input"))
    )
    (net (code "101") (name "unconnected-(D5A-C2{slash}ODT1-PadF2)") (class "Default")
      (node (ref "D5") (pin "F2") (pinfunction "C2/ODT1_F2") (pintype "input"))
    )
    (net (code "102") (name "unconnected-(D5A-NF,_NF{slash}TDQS_C-PadA3)") (class "Default")
      (node (ref "D5") (pin "A3") (pinfunction "NF,_NF/TDQS_C_A3") (pintype "output"))
    )
  )
)
